# cryptoshield.net
KiCad netlist of a schematic drawn in EAGLE
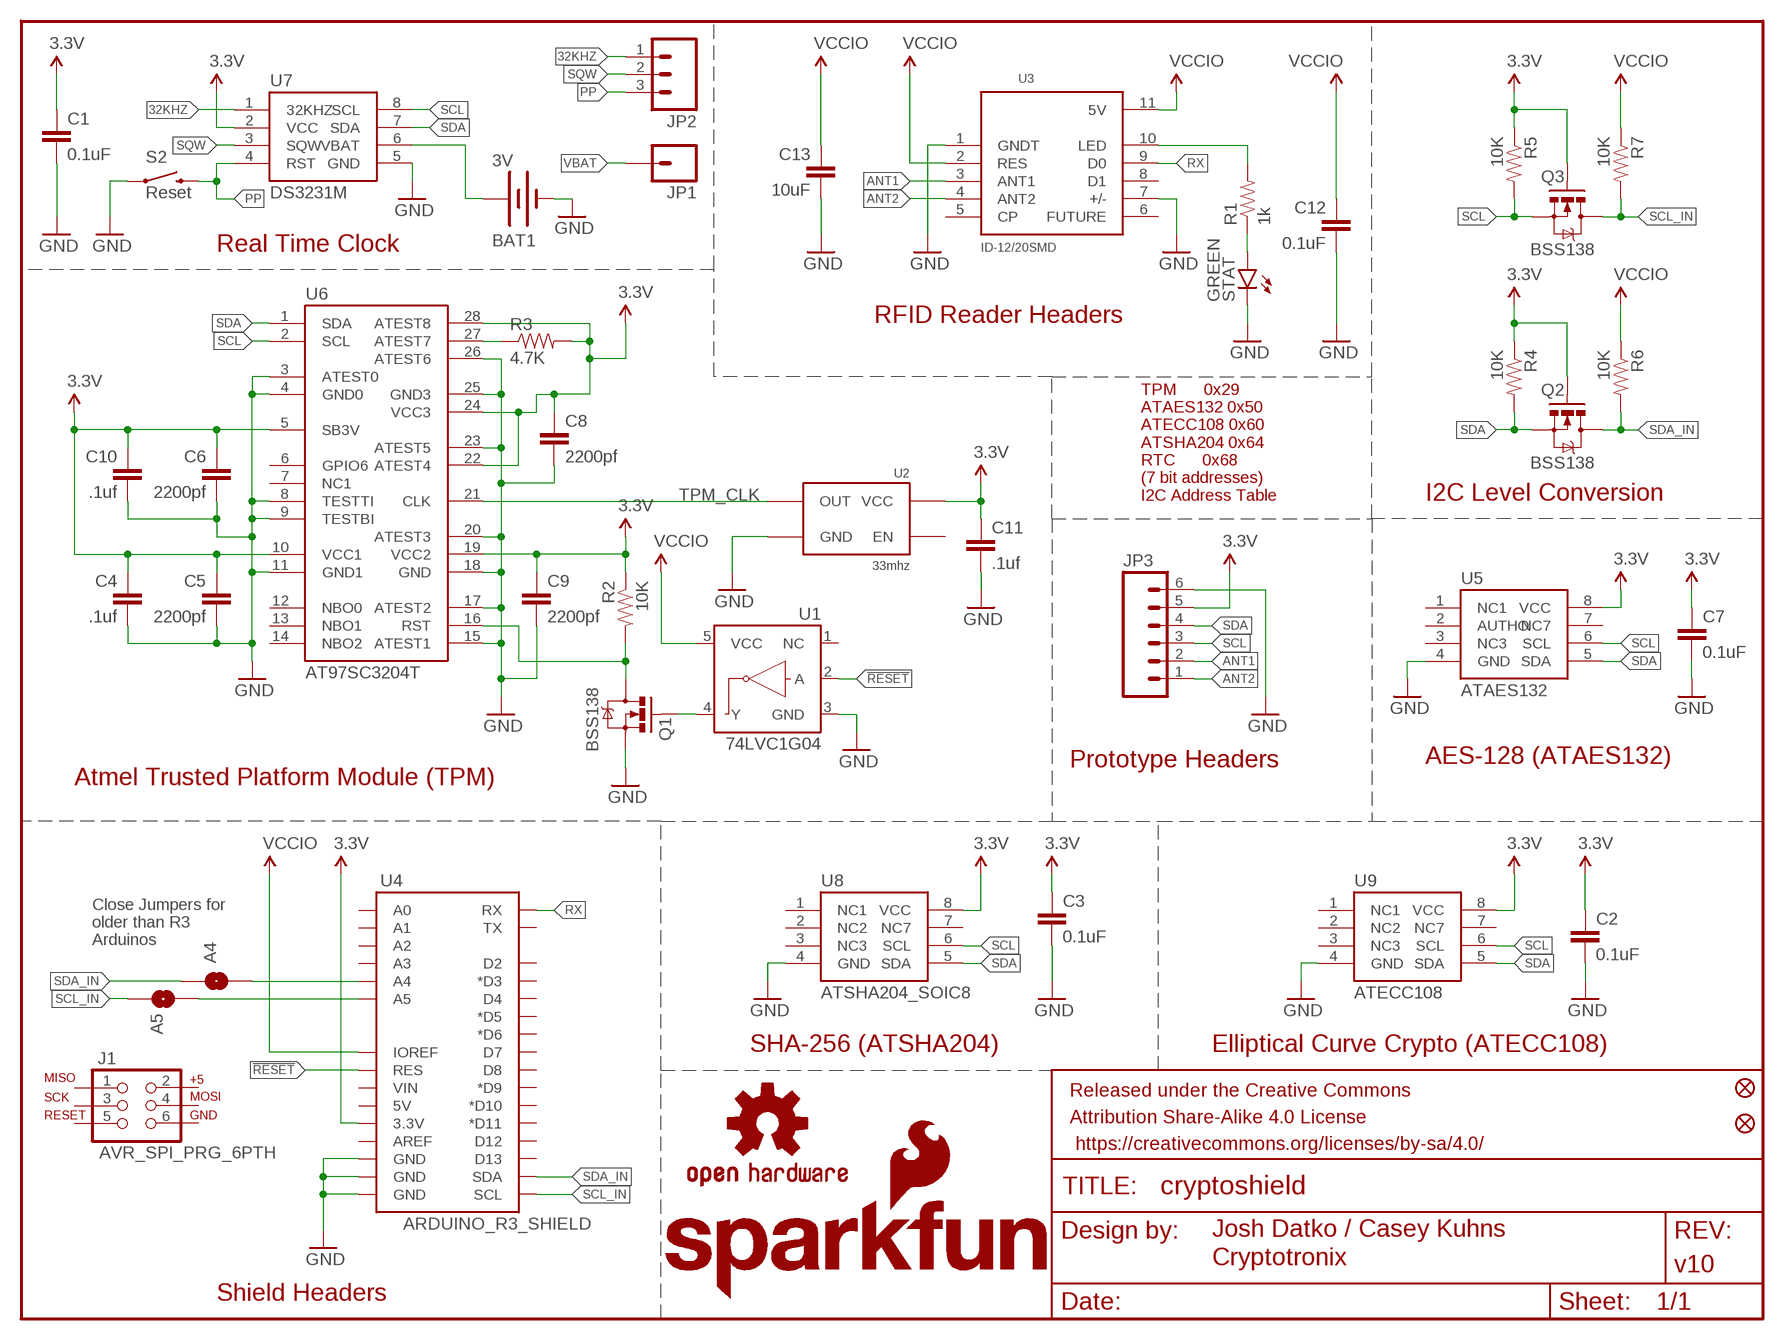
[diagram p0: schematic, sheet 1]

(export (version "E")
  (design (tool "Eeschema 10.0.6"))
  (components
    (comp (ref "A4")
      (value "JUMPER-PAD-2-NOYES_SILK")
      (footprint "eagle-import:PAD-JUMPER-2-NO_YES_SILK")
      (libsource (lib "eagle-import") (part "JUMPER-PAD-2-NOYES_SILK"))
    )
    (comp (ref "A5")
      (value "JUMPER-PAD-2-NOYES_SILK")
      (footprint "eagle-import:PAD-JUMPER-2-NO_YES_SILK")
      (libsource (lib "eagle-import") (part "JUMPER-PAD-2-NOYES_SILK"))
    )
    (comp (ref "BAT1")
      (value "3V")
      (footprint "eagle-import:BATTCON_12MM")
      (libsource (lib "eagle-import") (part "BATTERY12MM"))
    )
    (comp (ref "C1")
      (value "0.1uF")
      (footprint "eagle-import:0603-CAP")
      (libsource (lib "eagle-import") (part "0.1UF-25V(+80/-20%)(0603)"))
    )
    (comp (ref "C2")
      (value "0.1uF")
      (footprint "eagle-import:0603-CAP")
      (libsource (lib "eagle-import") (part "0.1UF-25V(+80/-20%)(0603)"))
    )
    (comp (ref "C3")
      (value "0.1uF")
      (footprint "eagle-import:0603-CAP")
      (libsource (lib "eagle-import") (part "0.1UF-25V(+80/-20%)(0603)"))
    )
    (comp (ref "C4")
      (value ".1uf")
      (footprint "eagle-import:0603-CAP")
      (libsource (lib "eagle-import") (part "0.1UF-25V(+80/-20%)(0603)"))
    )
    (comp (ref "C5")
      (value "2200pf")
      (footprint "eagle-import:0603-CAP")
      (libsource (lib "eagle-import") (part "2.2NF/2200PF-50V-10%(0603)"))
    )
    (comp (ref "C6")
      (value "2200pf")
      (footprint "eagle-import:0603-CAP")
      (libsource (lib "eagle-import") (part "2.2NF/2200PF-50V-10%(0603)"))
    )
    (comp (ref "C7")
      (value "0.1uF")
      (footprint "eagle-import:0603-CAP")
      (libsource (lib "eagle-import") (part "0.1UF-25V(+80/-20%)(0603)"))
    )
    (comp (ref "C8")
      (value "2200pf")
      (footprint "eagle-import:0603-CAP")
      (libsource (lib "eagle-import") (part "2.2NF/2200PF-50V-10%(0603)"))
    )
    (comp (ref "C9")
      (value "2200pf")
      (footprint "eagle-import:0603-CAP")
      (libsource (lib "eagle-import") (part "2.2NF/2200PF-50V-10%(0603)"))
    )
    (comp (ref "C10")
      (value ".1uf")
      (footprint "eagle-import:0603-CAP")
      (libsource (lib "eagle-import") (part "0.1UF-25V(+80/-20%)(0603)"))
    )
    (comp (ref "C11")
      (value ".1uf")
      (footprint "eagle-import:0603-CAP")
      (libsource (lib "eagle-import") (part "0.1UF-25V(+80/-20%)(0603)"))
    )
    (comp (ref "C12")
      (value "0.1uF")
      (footprint "eagle-import:0603-CAP")
      (libsource (lib "eagle-import") (part "0.1UF-25V(+80/-20%)(0603)"))
    )
    (comp (ref "C13")
      (value "10uF")
      (footprint "eagle-import:1210")
      (libsource (lib "eagle-import") (part "10UF50V20%(1210)"))
    )
    (comp (ref "FID1")
      (value "FIDUCIAL1X2")
      (footprint "eagle-import:FIDUCIAL-1X2")
      (libsource (lib "eagle-import") (part "FIDUCIAL1X2"))
    )
    (comp (ref "FID2")
      (value "FIDUCIAL1X2")
      (footprint "eagle-import:FIDUCIAL-1X2")
      (libsource (lib "eagle-import") (part "FIDUCIAL1X2"))
    )
    (comp (ref "FRAME2")
      (value "FRAME-LETTER")
      (footprint "eagle-import:CREATIVE_COMMONS")
      (fields (field (name "DESIGNER") "Josh Datko / Casey Kuhns") (field (name "VERSION") "v10"))
      (libsource (lib "eagle-import") (part "FRAME-LETTER"))
    )
    (comp (ref "J1")
      (value "AVR_SPI_PRG_6PTH")
      (footprint "eagle-import:2X3")
      (libsource (lib "eagle-import") (part "AVR_SPI_PRG_6PTH"))
    )
    (comp (ref "JP1")
      (value "M01PTH")
      (footprint "eagle-import:1X01")
      (libsource (lib "eagle-import") (part "M01PTH"))
    )
    (comp (ref "JP2")
      (value "M03PTH")
      (footprint "eagle-import:1X03")
      (libsource (lib "eagle-import") (part "M03PTH"))
    )
    (comp (ref "JP3")
      (value "M06NO_SILK_FEMALE_PTH")
      (footprint "eagle-import:1X06_NO_SILK")
      (libsource (lib "eagle-import") (part "M06NO_SILK_FEMALE_PTH"))
    )
    (comp (ref "LOGO2")
      (value "OSHW-LOGOS")
      (footprint "eagle-import:OSHW-LOGO-S")
      (libsource (lib "eagle-import") (part "OSHW-LOGOS"))
    )
    (comp (ref "LOGO3")
      (value "SFE_LOGO_NAME_FLAME.1_INCH")
      (footprint "eagle-import:SFE_LOGO_NAME_FLAME_.1")
      (libsource (lib "eagle-import") (part "SFE_LOGO_NAME_FLAME.1_INCH"))
    )
    (comp (ref "Q1")
      (value "BSS138")
      (footprint "eagle-import:SOT23-3")
      (libsource (lib "eagle-import") (part "MOSFET-NCHANNELBSS138"))
    )
    (comp (ref "Q2")
      (value "BSS138")
      (footprint "eagle-import:SOT23-3")
      (libsource (lib "eagle-import") (part "MOSFET-NCHANNELBSS138"))
    )
    (comp (ref "Q3")
      (value "BSS138")
      (footprint "eagle-import:SOT23-3")
      (libsource (lib "eagle-import") (part "MOSFET-NCHANNELBSS138"))
    )
    (comp (ref "R1")
      (value "1k")
      (footprint "eagle-import:0603-RES")
      (libsource (lib "eagle-import") (part "1K-1%"))
    )
    (comp (ref "R2")
      (value "10K")
      (footprint "eagle-import:0603-RES")
      (libsource (lib "eagle-import") (part "10KOHM-1/10W-1%(0603)0603"))
    )
    (comp (ref "R3")
      (value "4.7K")
      (footprint "eagle-import:0603")
      (libsource (lib "eagle-import") (part "4.7KOHM1/10W1%(0603)"))
    )
    (comp (ref "R4")
      (value "10K")
      (footprint "eagle-import:0603-RES")
      (libsource (lib "eagle-import") (part "10KOHM-1/10W-1%(0603)0603"))
    )
    (comp (ref "R5")
      (value "10K")
      (footprint "eagle-import:0603-RES")
      (libsource (lib "eagle-import") (part "10KOHM-1/10W-1%(0603)0603"))
    )
    (comp (ref "R6")
      (value "10K")
      (footprint "eagle-import:0603-RES")
      (libsource (lib "eagle-import") (part "10KOHM-1/10W-1%(0603)0603"))
    )
    (comp (ref "R7")
      (value "10K")
      (footprint "eagle-import:0603-RES")
      (libsource (lib "eagle-import") (part "10KOHM-1/10W-1%(0603)0603"))
    )
    (comp (ref "S2")
      (value "Reset")
      (footprint "eagle-import:TACTILE-SWITCH-SMD")
      (libsource (lib "eagle-import") (part "SWITCH-MOMENTARY-2SMD"))
    )
    (comp (ref "STAT")
      (value "GREEN")
      (footprint "eagle-import:LED-0603")
      (libsource (lib "eagle-import") (part "LED-GREEN0603"))
    )
    (comp (ref "U1")
      (value "74LVC1G04")
      (footprint "eagle-import:SOT353")
      (libsource (lib "eagle-import") (part "INVERTER_SOT353-5"))
    )
    (comp (ref "U2")
      (value "33mhz")
      (footprint "eagle-import:CRYSTAL-OSC-SMD-5X3.2")
      (libsource (lib "eagle-import") (part "33MHZ-OSCILLATOR"))
    )
    (comp (ref "U3")
      (value "ID-12/20SMD")
      (footprint "eagle-import:ID-12_SMD")
      (libsource (lib "eagle-import") (part "ID-12/20SMD"))
    )
    (comp (ref "U4")
      (value "ARDUINO_R3_SHIELD")
      (footprint "eagle-import:UNO_R3_SHIELD")
      (libsource (lib "eagle-import") (part "ARDUINO_R3_SHIELD"))
    )
    (comp (ref "U5")
      (value "ATAES132")
      (footprint "eagle-import:SOIC8")
      (libsource (lib "eagle-import") (part "ATAES132"))
    )
    (comp (ref "U6")
      (value "AT97SC3204T")
      (footprint "eagle-import:TSSOP28")
      (libsource (lib "eagle-import") (part "AT97SC3204T"))
    )
    (comp (ref "U7")
      (value "DS3231M")
      (footprint "eagle-import:SOIC8")
      (libsource (lib "eagle-import") (part "DS3231M"))
    )
    (comp (ref "U8")
      (value "ATSHA204_SOIC8")
      (footprint "eagle-import:SOIC8")
      (libsource (lib "eagle-import") (part "ATSHA204_SOIC8"))
    )
    (comp (ref "U9")
      (value "ATECC108")
      (footprint "eagle-import:SOIC8")
      (libsource (lib "eagle-import") (part "ATECC108"))
    )
  )
  (nets
    (net (code "1") (name "/TPM_CLK") (class "Default")
      (node (ref "U2") (pin "3") (pinfunction "OUT_3") (pintype "bidirectional"))
      (node (ref "U6") (pin "21") (pinfunction "CLK_21") (pintype "bidirectional"))
    )
    (net (code "2") (name "/~{RESET}") (class "Default")
      (node (ref "U1") (pin "2") (pinfunction "A_2") (pintype "bidirectional"))
      (node (ref "U4") (pin "RES") (pinfunction "RES_RES") (pintype "bidirectional"))
    )
    (net (code "3") (name "3.3V") (class "Default")
      (node (ref "C1") (pin "1") (pinfunction "1_1") (pintype "passive"))
      (node (ref "C10") (pin "1") (pinfunction "1_1") (pintype "passive"))
      (node (ref "C11") (pin "1") (pinfunction "1_1") (pintype "passive"))
      (node (ref "C2") (pin "1") (pinfunction "1_1") (pintype "passive"))
      (node (ref "C3") (pin "1") (pinfunction "1_1") (pintype "passive"))
      (node (ref "C4") (pin "1") (pinfunction "1_1") (pintype "passive"))
      (node (ref "C5") (pin "1") (pinfunction "1_1") (pintype "passive"))
      (node (ref "C6") (pin "1") (pinfunction "1_1") (pintype "passive"))
      (node (ref "C7") (pin "1") (pinfunction "1_1") (pintype "passive"))
      (node (ref "C8") (pin "1") (pinfunction "1_1") (pintype "passive"))
      (node (ref "C9") (pin "1") (pinfunction "1_1") (pintype "passive"))
      (node (ref "JP3") (pin "5") (pinfunction "5_5") (pintype "passive"))
      (node (ref "Q2") (pin "1") (pinfunction "G_1") (pintype "passive"))
      (node (ref "Q3") (pin "1") (pinfunction "G_1") (pintype "passive"))
      (node (ref "R2") (pin "1") (pinfunction "1_1") (pintype "passive"))
      (node (ref "R3") (pin "2") (pinfunction "2_2") (pintype "passive"))
      (node (ref "R4") (pin "1") (pinfunction "1_1") (pintype "passive"))
      (node (ref "R5") (pin "1") (pinfunction "1_1") (pintype "passive"))
      (node (ref "U2") (pin "4") (pinfunction "VCC_4") (pintype "bidirectional"))
      (node (ref "U4") (pin "3.3V") (pinfunction "3.3V_3.3V") (pintype "bidirectional"))
      (node (ref "U5") (pin "8") (pinfunction "VCC_8") (pintype "power_in"))
      (node (ref "U6") (pin "10") (pinfunction "VCC1_10") (pintype "power_in"))
      (node (ref "U6") (pin "19") (pinfunction "VCC2_19") (pintype "power_in"))
      (node (ref "U6") (pin "22") (pinfunction "ATEST4_22") (pintype "power_in"))
      (node (ref "U6") (pin "24") (pinfunction "VCC3_24") (pintype "power_in"))
      (node (ref "U6") (pin "28") (pinfunction "ATEST8_28") (pintype "power_in"))
      (node (ref "U6") (pin "5") (pinfunction "SB3V_5") (pintype "power_in"))
      (node (ref "U7") (pin "2") (pinfunction "VCC_2") (pintype "power_in"))
      (node (ref "U8") (pin "8") (pinfunction "VCC_8") (pintype "power_in"))
      (node (ref "U9") (pin "8") (pinfunction "VCC_8") (pintype "power_in"))
    )
    (net (code "4") (name "32KHZ") (class "Default")
      (node (ref "JP2") (pin "1") (pinfunction "1_1") (pintype "passive"))
      (node (ref "U7") (pin "1") (pinfunction "32KHZ_1") (pintype "output"))
    )
    (net (code "5") (name "ANT1") (class "Default")
      (node (ref "JP3") (pin "2") (pinfunction "2_2") (pintype "passive"))
      (node (ref "U3") (pin "3") (pinfunction "ANT1_3") (pintype "bidirectional"))
    )
    (net (code "6") (name "ANT2") (class "Default")
      (node (ref "JP3") (pin "1") (pinfunction "1_1") (pintype "passive"))
      (node (ref "U3") (pin "4") (pinfunction "ANT2_4") (pintype "bidirectional"))
    )
    (net (code "7") (name "GND") (class "Default")
      (node (ref "BAT1") (pin "GND") (pinfunction "-_GND") (pintype "power_in"))
      (node (ref "C1") (pin "2") (pinfunction "2_2") (pintype "passive"))
      (node (ref "C10") (pin "2") (pinfunction "2_2") (pintype "passive"))
      (node (ref "C11") (pin "2") (pinfunction "2_2") (pintype "passive"))
      (node (ref "C12") (pin "2") (pinfunction "2_2") (pintype "passive"))
      (node (ref "C13") (pin "2") (pinfunction "2_2") (pintype "passive"))
      (node (ref "C2") (pin "2") (pinfunction "2_2") (pintype "passive"))
      (node (ref "C3") (pin "2") (pinfunction "2_2") (pintype "passive"))
      (node (ref "C4") (pin "2") (pinfunction "2_2") (pintype "passive"))
      (node (ref "C5") (pin "2") (pinfunction "2_2") (pintype "passive"))
      (node (ref "C6") (pin "2") (pinfunction "2_2") (pintype "passive"))
      (node (ref "C7") (pin "2") (pinfunction "2_2") (pintype "passive"))
      (node (ref "C8") (pin "2") (pinfunction "2_2") (pintype "passive"))
      (node (ref "C9") (pin "2") (pinfunction "2_2") (pintype "passive"))
      (node (ref "JP3") (pin "6") (pinfunction "6_6") (pintype "passive"))
      (node (ref "Q1") (pin "2") (pinfunction "S_2") (pintype "passive"))
      (node (ref "S2") (pin "1") (pinfunction "1_1") (pintype "passive"))
      (node (ref "STAT") (pin "C") (pinfunction "C_C") (pintype "passive"))
      (node (ref "U1") (pin "3") (pinfunction "GND_3") (pintype "bidirectional"))
      (node (ref "U2") (pin "2") (pinfunction "GND_2") (pintype "bidirectional"))
      (node (ref "U3") (pin "1") (pinfunction "GNDT_1") (pintype "bidirectional"))
      (node (ref "U3") (pin "7") (pinfunction "+/-_7") (pintype "bidirectional"))
      (node (ref "U4") (pin "GND@0") (pinfunction "GND_GND@0") (pintype "bidirectional"))
      (node (ref "U4") (pin "GND@1") (pinfunction "GND_GND@1") (pintype "bidirectional"))
      (node (ref "U4") (pin "GND@2") (pinfunction "GND_GND@2") (pintype "bidirectional"))
      (node (ref "U5") (pin "4") (pinfunction "GND_4") (pintype "power_in"))
      (node (ref "U6") (pin "11") (pinfunction "GND1_11") (pintype "power_in"))
      (node (ref "U6") (pin "15") (pinfunction "ATEST1_15") (pintype "power_in"))
      (node (ref "U6") (pin "17") (pinfunction "ATEST2_17") (pintype "power_in"))
      (node (ref "U6") (pin "18") (pinfunction "GND_18") (pintype "power_in"))
      (node (ref "U6") (pin "20") (pinfunction "ATEST3_20") (pintype "power_in"))
      (node (ref "U6") (pin "23") (pinfunction "ATEST5_23") (pintype "power_in"))
      (node (ref "U6") (pin "25") (pinfunction "GND3_25") (pintype "power_in"))
      (node (ref "U6") (pin "26") (pinfunction "ATEST6_26") (pintype "power_in"))
      (node (ref "U6") (pin "3") (pinfunction "ATEST0_3") (pintype "power_in"))
      (node (ref "U6") (pin "4") (pinfunction "GND0_4") (pintype "power_in"))
      (node (ref "U6") (pin "8") (pinfunction "TESTTI_8") (pintype "power_in"))
      (node (ref "U6") (pin "9") (pinfunction "TESTBI_9") (pintype "power_in"))
      (node (ref "U7") (pin "5") (pinfunction "GND_5") (pintype "power_in"))
      (node (ref "U8") (pin "4") (pinfunction "GND_4") (pintype "power_in"))
      (node (ref "U9") (pin "4") (pinfunction "GND_4") (pintype "power_in"))
    )
    (net (code "8") (name "Net-(A4-Pad2)") (class "Default")
      (node (ref "A4") (pin "2") (pinfunction "2_2") (pintype "passive"))
      (node (ref "U4") (pin "A4") (pinfunction "A4_A4") (pintype "bidirectional"))
    )
    (net (code "9") (name "Net-(A5-Pad2)") (class "Default")
      (node (ref "A5") (pin "2") (pinfunction "2_2") (pintype "passive"))
      (node (ref "U4") (pin "A5") (pinfunction "A5_A5") (pintype "bidirectional"))
    )
    (net (code "10") (name "Net-(Q1-D)") (class "Default")
      (node (ref "Q1") (pin "3") (pinfunction "D_3") (pintype "passive"))
      (node (ref "R2") (pin "2") (pinfunction "2_2") (pintype "passive"))
      (node (ref "U6") (pin "16") (pinfunction "RST_16") (pintype "bidirectional"))
    )
    (net (code "11") (name "Net-(Q1-G)") (class "Default")
      (node (ref "Q1") (pin "1") (pinfunction "G_1") (pintype "passive"))
      (node (ref "U1") (pin "4") (pinfunction "Y_4") (pintype "bidirectional"))
    )
    (net (code "12") (name "Net-(R1-Pad1)") (class "Default")
      (node (ref "R1") (pin "1") (pinfunction "1_1") (pintype "passive"))
      (node (ref "STAT") (pin "A") (pinfunction "A_A") (pintype "passive"))
    )
    (net (code "13") (name "Net-(U3-LED)") (class "Default")
      (node (ref "R1") (pin "2") (pinfunction "2_2") (pintype "passive"))
      (node (ref "U3") (pin "10") (pinfunction "LED_10") (pintype "bidirectional"))
    )
    (net (code "14") (name "Net-(U6-ATEST7)") (class "Default")
      (node (ref "R3") (pin "1") (pinfunction "1_1") (pintype "passive"))
      (node (ref "U6") (pin "27") (pinfunction "ATEST7_27") (pintype "power_in"))
    )
    (net (code "15") (name "PP") (class "Default")
      (node (ref "JP2") (pin "3") (pinfunction "3_3") (pintype "passive"))
      (node (ref "S2") (pin "3") (pinfunction "2_3") (pintype "passive"))
      (node (ref "U7") (pin "4") (pinfunction "RST_4") (pintype "bidirectional"))
    )
    (net (code "16") (name "RX") (class "Default")
      (node (ref "U3") (pin "9") (pinfunction "D0_9") (pintype "bidirectional"))
      (node (ref "U4") (pin "RX") (pinfunction "RX_RX") (pintype "bidirectional"))
    )
    (net (code "17") (name "SCL") (class "Default")
      (node (ref "JP3") (pin "3") (pinfunction "3_3") (pintype "passive"))
      (node (ref "Q3") (pin "2") (pinfunction "S_2") (pintype "passive"))
      (node (ref "R5") (pin "2") (pinfunction "2_2") (pintype "passive"))
      (node (ref "U5") (pin "6") (pinfunction "SCL_6") (pintype "bidirectional"))
      (node (ref "U6") (pin "2") (pinfunction "SCL_2") (pintype "bidirectional"))
      (node (ref "U7") (pin "8") (pinfunction "SCL_8") (pintype "bidirectional"))
      (node (ref "U8") (pin "6") (pinfunction "SCL_6") (pintype "bidirectional"))
      (node (ref "U9") (pin "6") (pinfunction "SCL_6") (pintype "bidirectional"))
    )
    (net (code "18") (name "SCL_IN") (class "Default")
      (node (ref "A5") (pin "1") (pinfunction "1_1") (pintype "passive"))
      (node (ref "Q3") (pin "3") (pinfunction "D_3") (pintype "passive"))
      (node (ref "R7") (pin "2") (pinfunction "2_2") (pintype "passive"))
      (node (ref "U4") (pin "SCL") (pinfunction "SCL_SCL") (pintype "bidirectional"))
    )
    (net (code "19") (name "SDA") (class "Default")
      (node (ref "JP3") (pin "4") (pinfunction "4_4") (pintype "passive"))
      (node (ref "Q2") (pin "2") (pinfunction "S_2") (pintype "passive"))
      (node (ref "R4") (pin "2") (pinfunction "2_2") (pintype "passive"))
      (node (ref "U5") (pin "5") (pinfunction "SDA_5") (pintype "bidirectional"))
      (node (ref "U6") (pin "1") (pinfunction "SDA_1") (pintype "bidirectional"))
      (node (ref "U7") (pin "7") (pinfunction "SDA_7") (pintype "bidirectional"))
      (node (ref "U8") (pin "5") (pinfunction "SDA_5") (pintype "bidirectional"))
      (node (ref "U9") (pin "5") (pinfunction "SDA_5") (pintype "bidirectional"))
    )
    (net (code "20") (name "SDA_IN") (class "Default")
      (node (ref "A4") (pin "1") (pinfunction "1_1") (pintype "passive"))
      (node (ref "Q2") (pin "3") (pinfunction "D_3") (pintype "passive"))
      (node (ref "R6") (pin "2") (pinfunction "2_2") (pintype "passive"))
      (node (ref "U4") (pin "SDA") (pinfunction "SDA_SDA") (pintype "bidirectional"))
    )
    (net (code "21") (name "SQW") (class "Default")
      (node (ref "JP2") (pin "2") (pinfunction "2_2") (pintype "passive"))
      (node (ref "U7") (pin "3") (pinfunction "SQW_3") (pintype "output"))
    )
    (net (code "22") (name "VBAT") (class "Default")
      (node (ref "BAT1") (pin "PWR@1") (pinfunction "+_PWR@1") (pintype "power_in"))
      (node (ref "JP1") (pin "1") (pinfunction "1_1") (pintype "passive"))
      (node (ref "U7") (pin "6") (pinfunction "VBAT_6") (pintype "power_in"))
    )
    (net (code "23") (name "VCCIO") (class "Default")
      (node (ref "C12") (pin "1") (pinfunction "1_1") (pintype "passive"))
      (node (ref "C13") (pin "1") (pinfunction "1_1") (pintype "passive"))
      (node (ref "R6") (pin "1") (pinfunction "1_1") (pintype "passive"))
      (node (ref "R7") (pin "1") (pinfunction "1_1") (pintype "passive"))
      (node (ref "U1") (pin "5") (pinfunction "VCC_5") (pintype "bidirectional"))
      (node (ref "U3") (pin "11") (pinfunction "5V_11") (pintype "bidirectional"))
      (node (ref "U3") (pin "2") (pinfunction "RES_2") (pintype "bidirectional"))
      (node (ref "U4") (pin "IOREF") (pinfunction "IOREF_IOREF") (pintype "bidirectional"))
    )
    (net (code "24") (name "unconnected-(J1-Pad1)") (class "Default")
      (node (ref "J1") (pin "1") (pinfunction "1_1") (pintype "passive"))
    )
    (net (code "25") (name "unconnected-(J1-Pad2)") (class "Default")
      (node (ref "J1") (pin "2") (pinfunction "2_2") (pintype "passive"))
    )
    (net (code "26") (name "unconnected-(J1-Pad3)") (class "Default")
      (node (ref "J1") (pin "3") (pinfunction "3_3") (pintype "passive"))
    )
    (net (code "27") (name "unconnected-(J1-Pad4)") (class "Default")
      (node (ref "J1") (pin "4") (pinfunction "4_4") (pintype "passive"))
    )
    (net (code "28") (name "unconnected-(J1-Pad5)") (class "Default")
      (node (ref "J1") (pin "5") (pinfunction "5_5") (pintype "passive"))
    )
    (net (code "29") (name "unconnected-(J1-Pad6)") (class "Default")
      (node (ref "J1") (pin "6") (pinfunction "6_6") (pintype "passive"))
    )
    (net (code "30") (name "unconnected-(U1-NC-Pad1)") (class "Default")
      (node (ref "U1") (pin "1") (pinfunction "NC_1") (pintype "bidirectional"))
    )
    (net (code "31") (name "unconnected-(U2-EN-Pad1)") (class "Default")
      (node (ref "U2") (pin "1") (pinfunction "EN_1") (pintype "bidirectional"))
    )
    (net (code "32") (name "unconnected-(U3-CP-Pad5)") (class "Default")
      (node (ref "U3") (pin "5") (pinfunction "CP_5") (pintype "bidirectional"))
    )
    (net (code "33") (name "unconnected-(U3-D1-Pad8)") (class "Default")
      (node (ref "U3") (pin "8") (pinfunction "D1_8") (pintype "bidirectional"))
    )
    (net (code "34") (name "unconnected-(U3-FUTURE-Pad6)") (class "Default")
      (node (ref "U3") (pin "6") (pinfunction "FUTURE_6") (pintype "bidirectional"))
    )
    (net (code "35") (name "unconnected-(U4-*D3-PadD3)") (class "Default")
      (node (ref "U4") (pin "D3") (pinfunction "*D3_D3") (pintype "bidirectional"))
    )
    (net (code "36") (name "unconnected-(U4-*D5-PadD5)") (class "Default")
      (node (ref "U4") (pin "D5") (pinfunction "*D5_D5") (pintype "bidirectional"))
    )
    (net (code "37") (name "unconnected-(U4-*D6-PadD6)") (class "Default")
      (node (ref "U4") (pin "D6") (pinfunction "*D6_D6") (pintype "bidirectional"))
    )
    (net (code "38") (name "unconnected-(U4-*D9-PadD9)") (class "Default")
      (node (ref "U4") (pin "D9") (pinfunction "*D9_D9") (pintype "bidirectional"))
    )
    (net (code "39") (name "unconnected-(U4-*D10-PadD10)") (class "Default")
      (node (ref "U4") (pin "D10") (pinfunction "*D10_D10") (pintype "bidirectional"))
    )
    (net (code "40") (name "unconnected-(U4-*D11-PadD11)") (class "Default")
      (node (ref "U4") (pin "D11") (pinfunction "*D11_D11") (pintype "bidirectional"))
    )
    (net (code "41") (name "unconnected-(U4-Pad5V)") (class "Default")
      (node (ref "U4") (pin "5V") (pinfunction "5V_5V") (pintype "bidirectional"))
    )
    (net (code "42") (name "unconnected-(U4-PadA0)") (class "Default")
      (node (ref "U4") (pin "A0") (pinfunction "A0_A0") (pintype "bidirectional"))
    )
    (net (code "43") (name "unconnected-(U4-PadA1)") (class "Default")
      (node (ref "U4") (pin "A1") (pinfunction "A1_A1") (pintype "bidirectional"))
    )
    (net (code "44") (name "unconnected-(U4-PadA2)") (class "Default")
      (node (ref "U4") (pin "A2") (pinfunction "A2_A2") (pintype "bidirectional"))
    )
    (net (code "45") (name "unconnected-(U4-PadA3)") (class "Default")
      (node (ref "U4") (pin "A3") (pinfunction "A3_A3") (pintype "bidirectional"))
    )
    (net (code "46") (name "unconnected-(U4-PadAREF)") (class "Default")
      (node (ref "U4") (pin "AREF") (pinfunction "AREF_AREF") (pintype "bidirectional"))
    )
    (net (code "47") (name "unconnected-(U4-PadD2)") (class "Default")
      (node (ref "U4") (pin "D2") (pinfunction "D2_D2") (pintype "bidirectional"))
    )
    (net (code "48") (name "unconnected-(U4-PadD4)") (class "Default")
      (node (ref "U4") (pin "D4") (pinfunction "D4_D4") (pintype "bidirectional"))
    )
    (net (code "49") (name "unconnected-(U4-PadD7)") (class "Default")
      (node (ref "U4") (pin "D7") (pinfunction "D7_D7") (pintype "bidirectional"))
    )
    (net (code "50") (name "unconnected-(U4-PadD8)") (class "Default")
      (node (ref "U4") (pin "D8") (pinfunction "D8_D8") (pintype "bidirectional"))
    )
    (net (code "51") (name "unconnected-(U4-PadD12)") (class "Default")
      (node (ref "U4") (pin "D12") (pinfunction "D12_D12") (pintype "bidirectional"))
    )
    (net (code "52") (name "unconnected-(U4-PadD13)") (class "Default")
      (node (ref "U4") (pin "D13") (pinfunction "D13_D13") (pintype "bidirectional"))
    )
    (net (code "53") (name "unconnected-(U4-PadTX)") (class "Default")
      (node (ref "U4") (pin "TX") (pinfunction "TX_TX") (pintype "bidirectional"))
    )
    (net (code "54") (name "unconnected-(U4-PadVIN)") (class "Default")
      (node (ref "U4") (pin "VIN") (pinfunction "VIN_VIN") (pintype "bidirectional"))
    )
    (net (code "55") (name "unconnected-(U5-AUTHO-Pad2)") (class "Default")
      (node (ref "U5") (pin "2") (pinfunction "AUTHO_2") (pintype "bidirectional"))
    )
    (net (code "56") (name "unconnected-(U5-NC1-Pad1)") (class "Default")
      (node (ref "U5") (pin "1") (pinfunction "NC1_1") (pintype "no_connect"))
    )
    (net (code "57") (name "unconnected-(U5-NC3-Pad3)") (class "Default")
      (node (ref "U5") (pin "3") (pinfunction "NC3_3") (pintype "no_connect"))
    )
    (net (code "58") (name "unconnected-(U5-NC7-Pad7)") (class "Default")
      (node (ref "U5") (pin "7") (pinfunction "NC7_7") (pintype "no_connect"))
    )
    (net (code "59") (name "unconnected-(U6-GPIO6-Pad6)") (class "Default")
      (node (ref "U6") (pin "6") (pinfunction "GPIO6_6") (pintype "bidirectional"))
    )
    (net (code "60") (name "unconnected-(U6-NBO0-Pad12)") (class "Default")
      (node (ref "U6") (pin "12") (pinfunction "NBO0_12") (pintype "no_connect"))
    )
    (net (code "61") (name "unconnected-(U6-NBO1-Pad13)") (class "Default")
      (node (ref "U6") (pin "13") (pinfunction "NBO1_13") (pintype "no_connect"))
    )
    (net (code "62") (name "unconnected-(U6-NBO2-Pad14)") (class "Default")
      (node (ref "U6") (pin "14") (pinfunction "NBO2_14") (pintype "no_connect"))
    )
    (net (code "63") (name "unconnected-(U6-NC1-Pad7)") (class "Default")
      (node (ref "U6") (pin "7") (pinfunction "NC1_7") (pintype "no_connect"))
    )
    (net (code "64") (name "unconnected-(U8-NC1-Pad1)") (class "Default")
      (node (ref "U8") (pin "1") (pinfunction "NC1_1") (pintype "no_connect"))
    )
    (net (code "65") (name "unconnected-(U8-NC2-Pad2)") (class "Default")
      (node (ref "U8") (pin "2") (pinfunction "NC2_2") (pintype "no_connect"))
    )
    (net (code "66") (name "unconnected-(U8-NC3-Pad3)") (class "Default")
      (node (ref "U8") (pin "3") (pinfunction "NC3_3") (pintype "no_connect"))
    )
    (net (code "67") (name "unconnected-(U8-NC7-Pad7)") (class "Default")
      (node (ref "U8") (pin "7") (pinfunction "NC7_7") (pintype "no_connect"))
    )
    (net (code "68") (name "unconnected-(U9-NC1-Pad1)") (class "Default")
      (node (ref "U9") (pin "1") (pinfunction "NC1_1") (pintype "bidirectional"))
    )
    (net (code "69") (name "unconnected-(U9-NC2-Pad2)") (class "Default")
      (node (ref "U9") (pin "2") (pinfunction "NC2_2") (pintype "no_connect"))
    )
    (net (code "70") (name "unconnected-(U9-NC3-Pad3)") (class "Default")
      (node (ref "U9") (pin "3") (pinfunction "NC3_3") (pintype "no_connect"))
    )
    (net (code "71") (name "unconnected-(U9-NC7-Pad7)") (class "Default")
      (node (ref "U9") (pin "7") (pinfunction "NC7_7") (pintype "no_connect"))
    )
  )
)
